# Schematic.net
KiCad netlist of a schematic drawn in Altium Designer
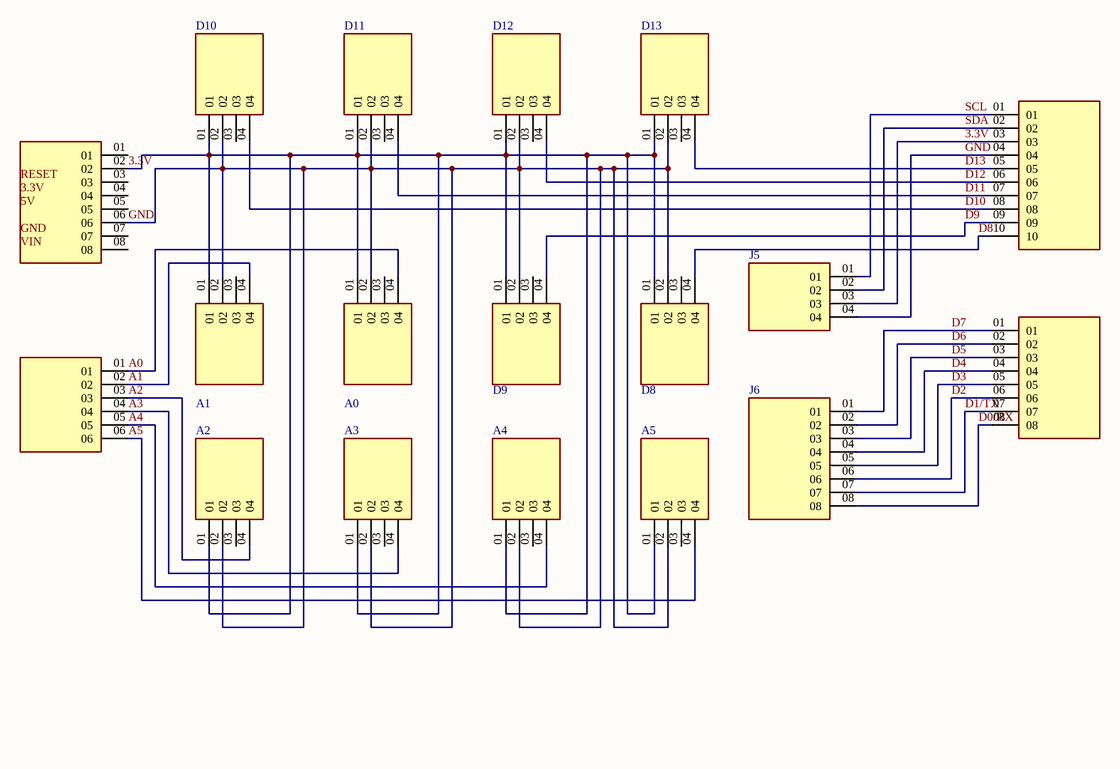
[diagram p0: Schematic.SchDoc]

(export (version "E")
  (design (tool "Eeschema 10.0.6"))
  (components
    (comp (ref "A0")
      (value "TSW-104-08-L-S-LL")
      (footprint "SAMTEC_TSW-104-08-L-S-LL")
      (libsource (lib "") (part "TSW-104-08-L-S-LL_2"))
    )
    (comp (ref "A1")
      (value "TSW-104-08-L-S-LL")
      (footprint "SAMTEC_TSW-104-08-L-S-LL")
      (libsource (lib "") (part "TSW-104-08-L-S-LL_2"))
    )
    (comp (ref "A2")
      (value "TSW-104-08-L-S-LL")
      (footprint "SAMTEC_TSW-104-08-L-S-LL")
      (libsource (lib "") (part "TSW-104-08-L-S-LL_1"))
    )
    (comp (ref "A3")
      (value "TSW-104-08-L-S-LL")
      (footprint "SAMTEC_TSW-104-08-L-S-LL")
      (libsource (lib "") (part "TSW-104-08-L-S-LL_1"))
    )
    (comp (ref "A4")
      (value "TSW-104-08-L-S-LL")
      (footprint "SAMTEC_TSW-104-08-L-S-LL")
      (libsource (lib "") (part "TSW-104-08-L-S-LL_1"))
    )
    (comp (ref "A5")
      (value "TSW-104-08-L-S-LL")
      (footprint "SAMTEC_TSW-104-08-L-S-LL")
      (libsource (lib "") (part "TSW-104-08-L-S-LL_1"))
    )
    (comp (ref "D8")
      (value "TSW-104-08-L-S-LL")
      (footprint "SAMTEC_TSW-104-08-L-S-LL")
      (libsource (lib "") (part "TSW-104-08-L-S-LL_2"))
    )
    (comp (ref "D9")
      (value "TSW-104-08-L-S-LL")
      (footprint "SAMTEC_TSW-104-08-L-S-LL")
      (libsource (lib "") (part "TSW-104-08-L-S-LL_2"))
    )
    (comp (ref "D10")
      (value "TSW-104-08-L-S-LL")
      (footprint "SAMTEC_TSW-104-08-L-S-LL")
      (libsource (lib "") (part "TSW-104-08-L-S-LL_1"))
    )
    (comp (ref "D11")
      (value "TSW-104-08-L-S-LL")
      (footprint "SAMTEC_TSW-104-08-L-S-LL")
      (libsource (lib "") (part "TSW-104-08-L-S-LL_1"))
    )
    (comp (ref "D12")
      (value "TSW-104-08-L-S-LL")
      (footprint "SAMTEC_TSW-104-08-L-S-LL")
      (libsource (lib "") (part "TSW-104-08-L-S-LL_1"))
    )
    (comp (ref "D13")
      (value "TSW-104-08-L-S-LL")
      (footprint "SAMTEC_TSW-104-08-L-S-LL")
      (libsource (lib "") (part "TSW-104-08-L-S-LL_1"))
    )
    (comp (ref "Header6")
      (value "MTSW-106-08-T-S-300-LL")
      (footprint "SAMTEC_MTSW-106-08-T-S-300-LL")
      (libsource (lib "MTSW-106-08-T-S-300-LL") (part "MTSW-106-08-T-S-300-LL"))
    )
    (comp (ref "Header8-Left")
      (value "TSW-108-06-G-S-LL")
      (footprint "SAMTEC_TSW-108-06-G-S-LL")
      (libsource (lib "") (part "TSW-108-06-G-S-LL_1"))
    )
    (comp (ref "Header8-Right")
      (value "TSW-108-06-G-S-LL")
      (footprint "SAMTEC_TSW-108-06-G-S-LL")
      (libsource (lib "TSW-108-06-G-S-LL") (part "TSW-108-06-G-S-LL"))
    )
    (comp (ref "Header10")
      (value "MTSW-110-10-G-S-595")
      (footprint "SAMTEC_MTSW-110-10-G-S-595")
      (libsource (lib "MTSW-110-10-G-S-595") (part "MTSW-110-10-G-S-595"))
    )
    (comp (ref "J5")
      (value "TSW-104-08-L-S-LL")
      (footprint "SAMTEC_TSW-104-08-L-S-LL")
      (libsource (lib "TSW-104-08-L-S-LL") (part "TSW-104-08-L-S-LL"))
    )
    (comp (ref "J6")
      (value "TSW-108-06-G-S-LL")
      (footprint "SAMTEC_TSW-108-06-G-S-LL")
      (libsource (lib "") (part "TSW-108-06-G-S-LL_1"))
    )
  )
  (nets
    (net (code "1") (name "/3.3V") (class "Default")
      (node (ref "A0") (pin "01") (pinfunction "01_01") (pintype "passive"))
      (node (ref "A1") (pin "01") (pinfunction "01_01") (pintype "passive"))
      (node (ref "A2") (pin "01") (pinfunction "01_01") (pintype "passive"))
      (node (ref "A3") (pin "01") (pinfunction "01_01") (pintype "passive"))
      (node (ref "A4") (pin "01") (pinfunction "01_01") (pintype "passive"))
      (node (ref "A5") (pin "01") (pinfunction "01_01") (pintype "passive"))
      (node (ref "D10") (pin "01") (pinfunction "01_01") (pintype "passive"))
      (node (ref "D11") (pin "01") (pinfunction "01_01") (pintype "passive"))
      (node (ref "D12") (pin "01") (pinfunction "01_01") (pintype "passive"))
      (node (ref "D13") (pin "01") (pinfunction "01_01") (pintype "passive"))
      (node (ref "D8") (pin "01") (pinfunction "01_01") (pintype "passive"))
      (node (ref "D9") (pin "01") (pinfunction "01_01") (pintype "passive"))
      (node (ref "Header10") (pin "03") (pinfunction "03_03") (pintype "passive"))
      (node (ref "Header8-Left") (pin "02") (pinfunction "02_02") (pintype "passive"))
      (node (ref "J5") (pin "03") (pinfunction "03_03") (pintype "passive"))
    )
    (net (code "3") (name "/A0") (class "Default")
      (node (ref "A0") (pin "04") (pinfunction "04_04") (pintype "passive"))
      (node (ref "Header6") (pin "01") (pinfunction "01_01") (pintype "passive"))
    )
    (net (code "4") (name "/A1") (class "Default")
      (node (ref "A1") (pin "04") (pinfunction "04_04") (pintype "passive"))
      (node (ref "Header6") (pin "02") (pinfunction "02_02") (pintype "passive"))
    )
    (net (code "5") (name "/A2") (class "Default")
      (node (ref "A2") (pin "04") (pinfunction "04_04") (pintype "passive"))
      (node (ref "Header6") (pin "03") (pinfunction "03_03") (pintype "passive"))
    )
    (net (code "6") (name "/A3") (class "Default")
      (node (ref "A3") (pin "04") (pinfunction "04_04") (pintype "passive"))
      (node (ref "Header6") (pin "04") (pinfunction "04_04") (pintype "passive"))
    )
    (net (code "7") (name "/A4") (class "Default")
      (node (ref "A4") (pin "04") (pinfunction "04_04") (pintype "passive"))
      (node (ref "Header6") (pin "05") (pinfunction "05_05") (pintype "passive"))
    )
    (net (code "8") (name "/A5") (class "Default")
      (node (ref "A5") (pin "04") (pinfunction "04_04") (pintype "passive"))
      (node (ref "Header6") (pin "06") (pinfunction "06_06") (pintype "passive"))
    )
    (net (code "9") (name "/D0{slash}RX") (class "Default")
      (node (ref "Header8-Right") (pin "08") (pinfunction "08_08") (pintype "passive"))
      (node (ref "J6") (pin "08") (pinfunction "08_08") (pintype "passive"))
    )
    (net (code "10") (name "/D1{slash}TX") (class "Default")
      (node (ref "Header8-Right") (pin "07") (pinfunction "07_07") (pintype "passive"))
      (node (ref "J6") (pin "07") (pinfunction "07_07") (pintype "passive"))
    )
    (net (code "11") (name "/D2") (class "Default")
      (node (ref "Header8-Right") (pin "06") (pinfunction "06_06") (pintype "passive"))
      (node (ref "J6") (pin "06") (pinfunction "06_06") (pintype "passive"))
    )
    (net (code "12") (name "/D3") (class "Default")
      (node (ref "Header8-Right") (pin "05") (pinfunction "05_05") (pintype "passive"))
      (node (ref "J6") (pin "05") (pinfunction "05_05") (pintype "passive"))
    )
    (net (code "13") (name "/D4") (class "Default")
      (node (ref "Header8-Right") (pin "04") (pinfunction "04_04") (pintype "passive"))
      (node (ref "J6") (pin "04") (pinfunction "04_04") (pintype "passive"))
    )
    (net (code "14") (name "/D5") (class "Default")
      (node (ref "Header8-Right") (pin "03") (pinfunction "03_03") (pintype "passive"))
      (node (ref "J6") (pin "03") (pinfunction "03_03") (pintype "passive"))
    )
    (net (code "15") (name "/D6") (class "Default")
      (node (ref "Header8-Right") (pin "02") (pinfunction "02_02") (pintype "passive"))
      (node (ref "J6") (pin "02") (pinfunction "02_02") (pintype "passive"))
    )
    (net (code "16") (name "/D7") (class "Default")
      (node (ref "Header8-Right") (pin "01") (pinfunction "01_01") (pintype "passive"))
      (node (ref "J6") (pin "01") (pinfunction "01_01") (pintype "passive"))
    )
    (net (code "17") (name "/D8") (class "Default")
      (node (ref "D8") (pin "04") (pinfunction "04_04") (pintype "passive"))
      (node (ref "Header10") (pin "10") (pinfunction "10_10") (pintype "passive"))
    )
    (net (code "18") (name "/D9") (class "Default")
      (node (ref "D9") (pin "04") (pinfunction "04_04") (pintype "passive"))
      (node (ref "Header10") (pin "09") (pinfunction "09_09") (pintype "passive"))
    )
    (net (code "19") (name "/D10") (class "Default")
      (node (ref "D10") (pin "04") (pinfunction "04_04") (pintype "passive"))
      (node (ref "Header10") (pin "08") (pinfunction "08_08") (pintype "passive"))
    )
    (net (code "20") (name "/D11") (class "Default")
      (node (ref "D11") (pin "04") (pinfunction "04_04") (pintype "passive"))
      (node (ref "Header10") (pin "07") (pinfunction "07_07") (pintype "passive"))
    )
    (net (code "21") (name "/D12") (class "Default")
      (node (ref "D12") (pin "04") (pinfunction "04_04") (pintype "passive"))
      (node (ref "Header10") (pin "06") (pinfunction "06_06") (pintype "passive"))
    )
    (net (code "22") (name "/D13") (class "Default")
      (node (ref "D13") (pin "04") (pinfunction "04_04") (pintype "passive"))
      (node (ref "Header10") (pin "05") (pinfunction "05_05") (pintype "passive"))
    )
    (net (code "23") (name "/GND") (class "Default")
      (node (ref "A0") (pin "02") (pinfunction "02_02") (pintype "passive"))
      (node (ref "A1") (pin "02") (pinfunction "02_02") (pintype "passive"))
      (node (ref "A2") (pin "02") (pinfunction "02_02") (pintype "passive"))
      (node (ref "A3") (pin "02") (pinfunction "02_02") (pintype "passive"))
      (node (ref "A4") (pin "02") (pinfunction "02_02") (pintype "passive"))
      (node (ref "A5") (pin "02") (pinfunction "02_02") (pintype "passive"))
      (node (ref "D10") (pin "02") (pinfunction "02_02") (pintype "passive"))
      (node (ref "D11") (pin "02") (pinfunction "02_02") (pintype "passive"))
      (node (ref "D12") (pin "02") (pinfunction "02_02") (pintype "passive"))
      (node (ref "D13") (pin "02") (pinfunction "02_02") (pintype "passive"))
      (node (ref "D8") (pin "02") (pinfunction "02_02") (pintype "passive"))
      (node (ref "D9") (pin "02") (pinfunction "02_02") (pintype "passive"))
      (node (ref "Header10") (pin "04") (pinfunction "04_04") (pintype "passive"))
      (node (ref "Header8-Left") (pin "06") (pinfunction "06_06") (pintype "passive"))
      (node (ref "J5") (pin "04") (pinfunction "04_04") (pintype "passive"))
    )
    (net (code "25") (name "/SCL") (class "Default")
      (node (ref "Header10") (pin "01") (pinfunction "01_01") (pintype "passive"))
      (node (ref "J5") (pin "01") (pinfunction "01_01") (pintype "passive"))
    )
    (net (code "26") (name "/SDA") (class "Default")
      (node (ref "Header10") (pin "02") (pinfunction "02_02") (pintype "passive"))
      (node (ref "J5") (pin "02") (pinfunction "02_02") (pintype "passive"))
    )
    (net (code "28") (name "unconnected-(A0-Pad03)") (class "Default")
      (node (ref "A0") (pin "03") (pinfunction "03_03") (pintype "passive"))
    )
    (net (code "29") (name "unconnected-(A1-Pad03)") (class "Default")
      (node (ref "A1") (pin "03") (pinfunction "03_03") (pintype "passive"))
    )
    (net (code "30") (name "unconnected-(A2-Pad03)") (class "Default")
      (node (ref "A2") (pin "03") (pinfunction "03_03") (pintype "passive"))
    )
    (net (code "31") (name "unconnected-(A3-Pad03)") (class "Default")
      (node (ref "A3") (pin "03") (pinfunction "03_03") (pintype "passive"))
    )
    (net (code "32") (name "unconnected-(A4-Pad03)") (class "Default")
      (node (ref "A4") (pin "03") (pinfunction "03_03") (pintype "passive"))
    )
    (net (code "33") (name "unconnected-(A5-Pad03)") (class "Default")
      (node (ref "A5") (pin "03") (pinfunction "03_03") (pintype "passive"))
    )
    (net (code "34") (name "unconnected-(D8-Pad03)") (class "Default")
      (node (ref "D8") (pin "03") (pinfunction "03_03") (pintype "passive"))
    )
    (net (code "35") (name "unconnected-(D9-Pad03)") (class "Default")
      (node (ref "D9") (pin "03") (pinfunction "03_03") (pintype "passive"))
    )
    (net (code "36") (name "unconnected-(D10-Pad03)") (class "Default")
      (node (ref "D10") (pin "03") (pinfunction "03_03") (pintype "passive"))
    )
    (net (code "37") (name "unconnected-(D11-Pad03)") (class "Default")
      (node (ref "D11") (pin "03") (pinfunction "03_03") (pintype "passive"))
    )
    (net (code "38") (name "unconnected-(D12-Pad03)") (class "Default")
      (node (ref "D12") (pin "03") (pinfunction "03_03") (pintype "passive"))
    )
    (net (code "39") (name "unconnected-(D13-Pad03)") (class "Default")
      (node (ref "D13") (pin "03") (pinfunction "03_03") (pintype "passive"))
    )
    (net (code "40") (name "unconnected-(Header8-Left-Pad01)") (class "Default")
      (node (ref "Header8-Left") (pin "01") (pinfunction "01_01") (pintype "passive"))
    )
    (net (code "41") (name "unconnected-(Header8-Left-Pad03)") (class "Default")
      (node (ref "Header8-Left") (pin "03") (pinfunction "03_03") (pintype "passive"))
    )
    (net (code "42") (name "unconnected-(Header8-Left-Pad04)") (class "Default")
      (node (ref "Header8-Left") (pin "04") (pinfunction "04_04") (pintype "passive"))
    )
    (net (code "43") (name "unconnected-(Header8-Left-Pad05)") (class "Default")
      (node (ref "Header8-Left") (pin "05") (pinfunction "05_05") (pintype "passive"))
    )
    (net (code "44") (name "unconnected-(Header8-Left-Pad07)") (class "Default")
      (node (ref "Header8-Left") (pin "07") (pinfunction "07_07") (pintype "passive"))
    )
    (net (code "45") (name "unconnected-(Header8-Left-Pad08)") (class "Default")
      (node (ref "Header8-Left") (pin "08") (pinfunction "08_08") (pintype "passive"))
    )
  )
)
